# 13_CEP.net
KiCad netlist of a schematic drawn in Altium Designer
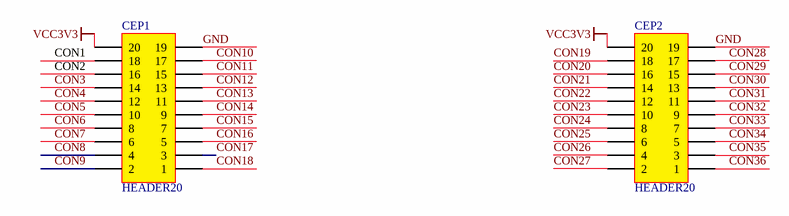
[diagram p0: 13_CEP.SchDoc]

(export (version "E")
  (design (tool "Eeschema 10.0.6"))
  (components
    (comp (ref "CEP1")
      (value "HEADER20")
      (footprint "HEADER10X2X2.5")
      (libsource (lib "jinrylib") (part "HEADER10X2"))
    )
    (comp (ref "CEP2")
      (value "HEADER20")
      (footprint "HEADER10X2X2.5")
      (libsource (lib "jinrylib") (part "HEADER10X2"))
    )
  )
  (nets
    (net (code "1") (name "/CON1") (class "Default")
      (node (ref "CEP1") (pin "18") (pinfunction "18_18") (pintype "passive"))
    )
    (net (code "2") (name "/CON2") (class "Default")
      (node (ref "CEP1") (pin "16") (pinfunction "16_16") (pintype "passive"))
    )
    (net (code "3") (name "/CON3") (class "Default")
      (node (ref "CEP1") (pin "14") (pinfunction "14_14") (pintype "passive"))
    )
    (net (code "4") (name "/CON4") (class "Default")
      (node (ref "CEP1") (pin "12") (pinfunction "12_12") (pintype "passive"))
    )
    (net (code "5") (name "/CON5") (class "Default")
      (node (ref "CEP1") (pin "10") (pinfunction "10_10") (pintype "passive"))
    )
    (net (code "6") (name "/CON6") (class "Default")
      (node (ref "CEP1") (pin "8") (pinfunction "8_8") (pintype "passive"))
    )
    (net (code "7") (name "/CON7") (class "Default")
      (node (ref "CEP1") (pin "6") (pinfunction "6_6") (pintype "passive"))
    )
    (net (code "8") (name "/CON8") (class "Default")
      (node (ref "CEP1") (pin "4") (pinfunction "4_4") (pintype "passive"))
    )
    (net (code "9") (name "/CON9") (class "Default")
      (node (ref "CEP1") (pin "2") (pinfunction "2_2") (pintype "passive"))
    )
    (net (code "10") (name "/CON10") (class "Default")
      (node (ref "CEP1") (pin "17") (pinfunction "17_17") (pintype "passive"))
    )
    (net (code "11") (name "/CON11") (class "Default")
      (node (ref "CEP1") (pin "15") (pinfunction "15_15") (pintype "passive"))
    )
    (net (code "12") (name "/CON12") (class "Default")
      (node (ref "CEP1") (pin "13") (pinfunction "13_13") (pintype "passive"))
    )
    (net (code "13") (name "/CON13") (class "Default")
      (node (ref "CEP1") (pin "11") (pinfunction "11_11") (pintype "passive"))
    )
    (net (code "14") (name "/CON14") (class "Default")
      (node (ref "CEP1") (pin "9") (pinfunction "9_9") (pintype "passive"))
    )
    (net (code "15") (name "/CON15") (class "Default")
      (node (ref "CEP1") (pin "7") (pinfunction "7_7") (pintype "passive"))
    )
    (net (code "16") (name "/CON16") (class "Default")
      (node (ref "CEP1") (pin "5") (pinfunction "5_5") (pintype "passive"))
    )
    (net (code "17") (name "/CON17") (class "Default")
      (node (ref "CEP1") (pin "3") (pinfunction "3_3") (pintype "passive"))
    )
    (net (code "18") (name "/CON18") (class "Default")
      (node (ref "CEP1") (pin "1") (pinfunction "1_1") (pintype "passive"))
    )
    (net (code "19") (name "/CON19") (class "Default")
      (node (ref "CEP2") (pin "18") (pinfunction "18_18") (pintype "passive"))
    )
    (net (code "20") (name "/CON20") (class "Default")
      (node (ref "CEP2") (pin "16") (pinfunction "16_16") (pintype "passive"))
    )
    (net (code "21") (name "/CON21") (class "Default")
      (node (ref "CEP2") (pin "14") (pinfunction "14_14") (pintype "passive"))
    )
    (net (code "22") (name "/CON22") (class "Default")
      (node (ref "CEP2") (pin "12") (pinfunction "12_12") (pintype "passive"))
    )
    (net (code "23") (name "/CON23") (class "Default")
      (node (ref "CEP2") (pin "10") (pinfunction "10_10") (pintype "passive"))
    )
    (net (code "24") (name "/CON24") (class "Default")
      (node (ref "CEP2") (pin "8") (pinfunction "8_8") (pintype "passive"))
    )
    (net (code "25") (name "/CON25") (class "Default")
      (node (ref "CEP2") (pin "6") (pinfunction "6_6") (pintype "passive"))
    )
    (net (code "26") (name "/CON26") (class "Default")
      (node (ref "CEP2") (pin "4") (pinfunction "4_4") (pintype "passive"))
    )
    (net (code "27") (name "/CON27") (class "Default")
      (node (ref "CEP2") (pin "2") (pinfunction "2_2") (pintype "passive"))
    )
    (net (code "28") (name "/CON28") (class "Default")
      (node (ref "CEP2") (pin "17") (pinfunction "17_17") (pintype "passive"))
    )
    (net (code "29") (name "/CON29") (class "Default")
      (node (ref "CEP2") (pin "15") (pinfunction "15_15") (pintype "passive"))
    )
    (net (code "30") (name "/CON30") (class "Default")
      (node (ref "CEP2") (pin "13") (pinfunction "13_13") (pintype "passive"))
    )
    (net (code "31") (name "/CON31") (class "Default")
      (node (ref "CEP2") (pin "11") (pinfunction "11_11") (pintype "passive"))
    )
    (net (code "32") (name "/CON32") (class "Default")
      (node (ref "CEP2") (pin "9") (pinfunction "9_9") (pintype "passive"))
    )
    (net (code "33") (name "/CON33") (class "Default")
      (node (ref "CEP2") (pin "7") (pinfunction "7_7") (pintype "passive"))
    )
    (net (code "34") (name "/CON34") (class "Default")
      (node (ref "CEP2") (pin "5") (pinfunction "5_5") (pintype "passive"))
    )
    (net (code "35") (name "/CON35") (class "Default")
      (node (ref "CEP2") (pin "3") (pinfunction "3_3") (pintype "passive"))
    )
    (net (code "36") (name "/CON36") (class "Default")
      (node (ref "CEP2") (pin "1") (pinfunction "1_1") (pintype "passive"))
    )
    (net (code "37") (name "/GND") (class "Default")
      (node (ref "CEP1") (pin "19") (pinfunction "19_19") (pintype "passive"))
      (node (ref "CEP2") (pin "19") (pinfunction "19_19") (pintype "passive"))
    )
    (net (code "38") (name "VCC3V3") (class "Default")
      (node (ref "CEP1") (pin "20") (pinfunction "20_20") (pintype "passive"))
      (node (ref "CEP2") (pin "20") (pinfunction "20_20") (pintype "passive"))
    )
  )
)
